# PHOTODIODE_SENSOR_8.net
KiCad netlist of a schematic drawn in EAGLE
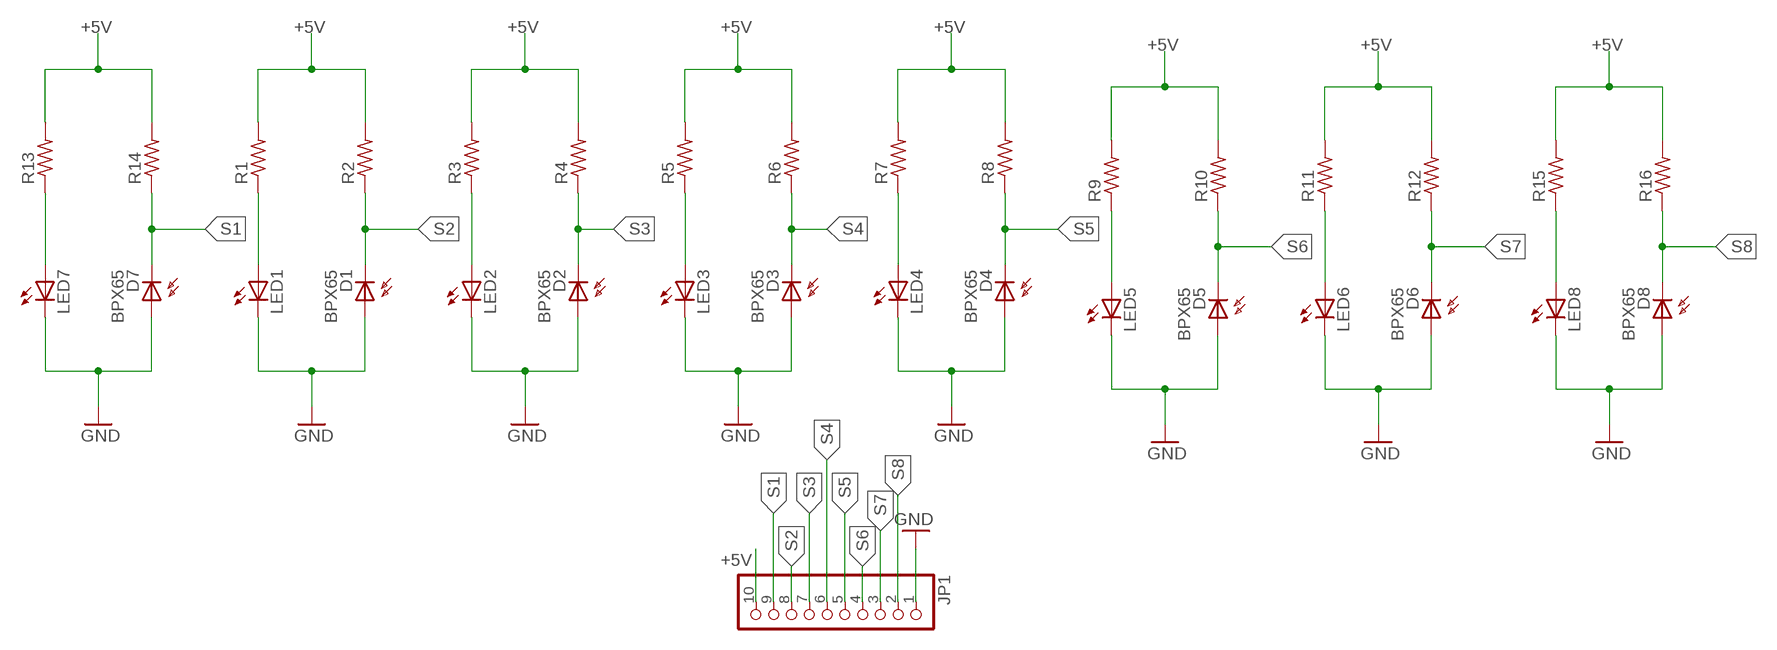
[diagram p0: schematic, sheet 1]

(export (version "E")
  (design (tool "Eeschema 10.0.6"))
  (components
    (comp (ref "D1")
      (value "BPX65")
      (footprint "eagle-import:BPX65")
      (fields (field (name "MPN") "BPX65."))
      (libsource (lib "eagle-import") (part "BPX65"))
    )
    (comp (ref "D2")
      (value "BPX65")
      (footprint "eagle-import:BPX65")
      (fields (field (name "MPN") "BPX65."))
      (libsource (lib "eagle-import") (part "BPX65"))
    )
    (comp (ref "D3")
      (value "BPX65")
      (footprint "eagle-import:BPX65")
      (fields (field (name "MPN") "BPX65."))
      (libsource (lib "eagle-import") (part "BPX65"))
    )
    (comp (ref "D4")
      (value "BPX65")
      (footprint "eagle-import:BPX65")
      (fields (field (name "MPN") "BPX65."))
      (libsource (lib "eagle-import") (part "BPX65"))
    )
    (comp (ref "D5")
      (value "BPX65")
      (footprint "eagle-import:BPX65")
      (fields (field (name "MPN") "BPX65."))
      (libsource (lib "eagle-import") (part "BPX65"))
    )
    (comp (ref "D6")
      (value "BPX65")
      (footprint "eagle-import:BPX65")
      (fields (field (name "MPN") "BPX65."))
      (libsource (lib "eagle-import") (part "BPX65"))
    )
    (comp (ref "D7")
      (value "BPX65")
      (footprint "eagle-import:BPX65")
      (fields (field (name "MPN") "BPX65."))
      (libsource (lib "eagle-import") (part "BPX65"))
    )
    (comp (ref "D8")
      (value "BPX65")
      (footprint "eagle-import:BPX65")
      (fields (field (name "MPN") "BPX65."))
      (libsource (lib "eagle-import") (part "BPX65"))
    )
    (comp (ref "JP1")
      (value "PINHD-1X10")
      (footprint "eagle-import:1X10")
      (libsource (lib "eagle-import") (part "PINHD-1X10"))
    )
    (comp (ref "LED1")
      (value "LED5MM")
      (footprint "eagle-import:LED5MM")
      (libsource (lib "eagle-import") (part "LED5MM"))
    )
    (comp (ref "LED2")
      (value "LED5MM")
      (footprint "eagle-import:LED5MM")
      (libsource (lib "eagle-import") (part "LED5MM"))
    )
    (comp (ref "LED3")
      (value "LED5MM")
      (footprint "eagle-import:LED5MM")
      (libsource (lib "eagle-import") (part "LED5MM"))
    )
    (comp (ref "LED4")
      (value "LED5MM")
      (footprint "eagle-import:LED5MM")
      (libsource (lib "eagle-import") (part "LED5MM"))
    )
    (comp (ref "LED5")
      (value "LED5MM")
      (footprint "eagle-import:LED5MM")
      (libsource (lib "eagle-import") (part "LED5MM"))
    )
    (comp (ref "LED6")
      (value "LED5MM")
      (footprint "eagle-import:LED5MM")
      (libsource (lib "eagle-import") (part "LED5MM"))
    )
    (comp (ref "LED7")
      (value "LED5MM")
      (footprint "eagle-import:LED5MM")
      (libsource (lib "eagle-import") (part "LED5MM"))
    )
    (comp (ref "LED8")
      (value "LED5MM")
      (footprint "eagle-import:LED5MM")
      (libsource (lib "eagle-import") (part "LED5MM"))
    )
    (comp (ref "R1")
      (value "R-US_0204/7")
      (footprint "eagle-import:0204_7")
      (libsource (lib "eagle-import") (part "R-US_0204/7"))
    )
    (comp (ref "R2")
      (value "R-US_0204/7")
      (footprint "eagle-import:0204_7")
      (libsource (lib "eagle-import") (part "R-US_0204/7"))
    )
    (comp (ref "R3")
      (value "R-US_0204/7")
      (footprint "eagle-import:0204_7")
      (libsource (lib "eagle-import") (part "R-US_0204/7"))
    )
    (comp (ref "R4")
      (value "R-US_0204/7")
      (footprint "eagle-import:0204_7")
      (libsource (lib "eagle-import") (part "R-US_0204/7"))
    )
    (comp (ref "R5")
      (value "R-US_0204/7")
      (footprint "eagle-import:0204_7")
      (libsource (lib "eagle-import") (part "R-US_0204/7"))
    )
    (comp (ref "R6")
      (value "R-US_0204/7")
      (footprint "eagle-import:0204_7")
      (libsource (lib "eagle-import") (part "R-US_0204/7"))
    )
    (comp (ref "R7")
      (value "R-US_0204/7")
      (footprint "eagle-import:0204_7")
      (libsource (lib "eagle-import") (part "R-US_0204/7"))
    )
    (comp (ref "R8")
      (value "R-US_0204/7")
      (footprint "eagle-import:0204_7")
      (libsource (lib "eagle-import") (part "R-US_0204/7"))
    )
    (comp (ref "R9")
      (value "R-US_0204/7")
      (footprint "eagle-import:0204_7")
      (libsource (lib "eagle-import") (part "R-US_0204/7"))
    )
    (comp (ref "R10")
      (value "R-US_0204/7")
      (footprint "eagle-import:0204_7")
      (libsource (lib "eagle-import") (part "R-US_0204/7"))
    )
    (comp (ref "R11")
      (value "R-US_0204/7")
      (footprint "eagle-import:0204_7")
      (libsource (lib "eagle-import") (part "R-US_0204/7"))
    )
    (comp (ref "R12")
      (value "R-US_0204/7")
      (footprint "eagle-import:0204_7")
      (libsource (lib "eagle-import") (part "R-US_0204/7"))
    )
    (comp (ref "R13")
      (value "R-US_0204/7")
      (footprint "eagle-import:0204_7")
      (libsource (lib "eagle-import") (part "R-US_0204/7"))
    )
    (comp (ref "R14")
      (value "R-US_0204/7")
      (footprint "eagle-import:0204_7")
      (libsource (lib "eagle-import") (part "R-US_0204/7"))
    )
    (comp (ref "R15")
      (value "R-US_0204/7")
      (footprint "eagle-import:0204_7")
      (libsource (lib "eagle-import") (part "R-US_0204/7"))
    )
    (comp (ref "R16")
      (value "R-US_0204/7")
      (footprint "eagle-import:0204_7")
      (libsource (lib "eagle-import") (part "R-US_0204/7"))
    )
  )
  (nets
    (net (code "1") (name "/+5V") (class "Default")
      (node (ref "JP1") (pin "10") (pinfunction "10_10") (pintype "passive"))
      (node (ref "R1") (pin "2") (pinfunction "2_2") (pintype "passive"))
      (node (ref "R10") (pin "2") (pinfunction "2_2") (pintype "passive"))
      (node (ref "R11") (pin "2") (pinfunction "2_2") (pintype "passive"))
      (node (ref "R12") (pin "2") (pinfunction "2_2") (pintype "passive"))
      (node (ref "R13") (pin "2") (pinfunction "2_2") (pintype "passive"))
      (node (ref "R14") (pin "2") (pinfunction "2_2") (pintype "passive"))
      (node (ref "R15") (pin "2") (pinfunction "2_2") (pintype "passive"))
      (node (ref "R16") (pin "2") (pinfunction "2_2") (pintype "passive"))
      (node (ref "R2") (pin "2") (pinfunction "2_2") (pintype "passive"))
      (node (ref "R3") (pin "2") (pinfunction "2_2") (pintype "passive"))
      (node (ref "R4") (pin "2") (pinfunction "2_2") (pintype "passive"))
      (node (ref "R5") (pin "2") (pinfunction "2_2") (pintype "passive"))
      (node (ref "R6") (pin "2") (pinfunction "2_2") (pintype "passive"))
      (node (ref "R7") (pin "2") (pinfunction "2_2") (pintype "passive"))
      (node (ref "R8") (pin "2") (pinfunction "2_2") (pintype "passive"))
      (node (ref "R9") (pin "2") (pinfunction "2_2") (pintype "passive"))
    )
    (net (code "2") (name "GND") (class "Default")
      (node (ref "D1") (pin "A") (pinfunction "A_A") (pintype "passive"))
      (node (ref "D2") (pin "A") (pinfunction "A_A") (pintype "passive"))
      (node (ref "D3") (pin "A") (pinfunction "A_A") (pintype "passive"))
      (node (ref "D4") (pin "A") (pinfunction "A_A") (pintype "passive"))
      (node (ref "D5") (pin "A") (pinfunction "A_A") (pintype "passive"))
      (node (ref "D6") (pin "A") (pinfunction "A_A") (pintype "passive"))
      (node (ref "D7") (pin "A") (pinfunction "A_A") (pintype "passive"))
      (node (ref "D8") (pin "A") (pinfunction "A_A") (pintype "passive"))
      (node (ref "JP1") (pin "1") (pinfunction "1_1") (pintype "passive"))
      (node (ref "LED1") (pin "K") (pinfunction "C_K") (pintype "passive"))
      (node (ref "LED2") (pin "K") (pinfunction "C_K") (pintype "passive"))
      (node (ref "LED3") (pin "K") (pinfunction "C_K") (pintype "passive"))
      (node (ref "LED4") (pin "K") (pinfunction "C_K") (pintype "passive"))
      (node (ref "LED5") (pin "K") (pinfunction "C_K") (pintype "passive"))
      (node (ref "LED6") (pin "K") (pinfunction "C_K") (pintype "passive"))
      (node (ref "LED7") (pin "K") (pinfunction "C_K") (pintype "passive"))
      (node (ref "LED8") (pin "K") (pinfunction "C_K") (pintype "passive"))
    )
    (net (code "3") (name "Net-(LED1-PadA)") (class "Default")
      (node (ref "LED1") (pin "A") (pinfunction "A_A") (pintype "passive"))
      (node (ref "R1") (pin "1") (pinfunction "1_1") (pintype "passive"))
    )
    (net (code "4") (name "Net-(LED2-PadA)") (class "Default")
      (node (ref "LED2") (pin "A") (pinfunction "A_A") (pintype "passive"))
      (node (ref "R3") (pin "1") (pinfunction "1_1") (pintype "passive"))
    )
    (net (code "5") (name "Net-(LED3-PadA)") (class "Default")
      (node (ref "LED3") (pin "A") (pinfunction "A_A") (pintype "passive"))
      (node (ref "R5") (pin "1") (pinfunction "1_1") (pintype "passive"))
    )
    (net (code "6") (name "Net-(LED4-PadA)") (class "Default")
      (node (ref "LED4") (pin "A") (pinfunction "A_A") (pintype "passive"))
      (node (ref "R7") (pin "1") (pinfunction "1_1") (pintype "passive"))
    )
    (net (code "7") (name "Net-(LED5-PadA)") (class "Default")
      (node (ref "LED5") (pin "A") (pinfunction "A_A") (pintype "passive"))
      (node (ref "R9") (pin "1") (pinfunction "1_1") (pintype "passive"))
    )
    (net (code "8") (name "Net-(LED6-PadA)") (class "Default")
      (node (ref "LED6") (pin "A") (pinfunction "A_A") (pintype "passive"))
      (node (ref "R11") (pin "1") (pinfunction "1_1") (pintype "passive"))
    )
    (net (code "9") (name "Net-(LED7-PadA)") (class "Default")
      (node (ref "LED7") (pin "A") (pinfunction "A_A") (pintype "passive"))
      (node (ref "R13") (pin "1") (pinfunction "1_1") (pintype "passive"))
    )
    (net (code "10") (name "Net-(LED8-PadA)") (class "Default")
      (node (ref "LED8") (pin "A") (pinfunction "A_A") (pintype "passive"))
      (node (ref "R15") (pin "1") (pinfunction "1_1") (pintype "passive"))
    )
    (net (code "11") (name "S1") (class "Default")
      (node (ref "D7") (pin "K") (pinfunction "C_K") (pintype "passive"))
      (node (ref "JP1") (pin "9") (pinfunction "9_9") (pintype "passive"))
      (node (ref "R14") (pin "1") (pinfunction "1_1") (pintype "passive"))
    )
    (net (code "12") (name "S2") (class "Default")
      (node (ref "D1") (pin "K") (pinfunction "C_K") (pintype "passive"))
      (node (ref "JP1") (pin "8") (pinfunction "8_8") (pintype "passive"))
      (node (ref "R2") (pin "1") (pinfunction "1_1") (pintype "passive"))
    )
    (net (code "13") (name "S3") (class "Default")
      (node (ref "D2") (pin "K") (pinfunction "C_K") (pintype "passive"))
      (node (ref "JP1") (pin "7") (pinfunction "7_7") (pintype "passive"))
      (node (ref "R4") (pin "1") (pinfunction "1_1") (pintype "passive"))
    )
    (net (code "14") (name "S4") (class "Default")
      (node (ref "D3") (pin "K") (pinfunction "C_K") (pintype "passive"))
      (node (ref "JP1") (pin "6") (pinfunction "6_6") (pintype "passive"))
      (node (ref "R6") (pin "1") (pinfunction "1_1") (pintype "passive"))
    )
    (net (code "15") (name "S5") (class "Default")
      (node (ref "D4") (pin "K") (pinfunction "C_K") (pintype "passive"))
      (node (ref "JP1") (pin "5") (pinfunction "5_5") (pintype "passive"))
      (node (ref "R8") (pin "1") (pinfunction "1_1") (pintype "passive"))
    )
    (net (code "16") (name "S6") (class "Default")
      (node (ref "D5") (pin "K") (pinfunction "C_K") (pintype "passive"))
      (node (ref "JP1") (pin "4") (pinfunction "4_4") (pintype "passive"))
      (node (ref "R10") (pin "1") (pinfunction "1_1") (pintype "passive"))
    )
    (net (code "17") (name "S7") (class "Default")
      (node (ref "D6") (pin "K") (pinfunction "C_K") (pintype "passive"))
      (node (ref "JP1") (pin "3") (pinfunction "3_3") (pintype "passive"))
      (node (ref "R12") (pin "1") (pinfunction "1_1") (pintype "passive"))
    )
    (net (code "18") (name "S8") (class "Default")
      (node (ref "D8") (pin "K") (pinfunction "C_K") (pintype "passive"))
      (node (ref "JP1") (pin "2") (pinfunction "2_2") (pintype "passive"))
      (node (ref "R16") (pin "1") (pinfunction "1_1") (pintype "passive"))
    )
  )
)
